# SparkFun_MOSFET_PetalV0_1.net
KiCad netlist of a schematic drawn in EAGLE
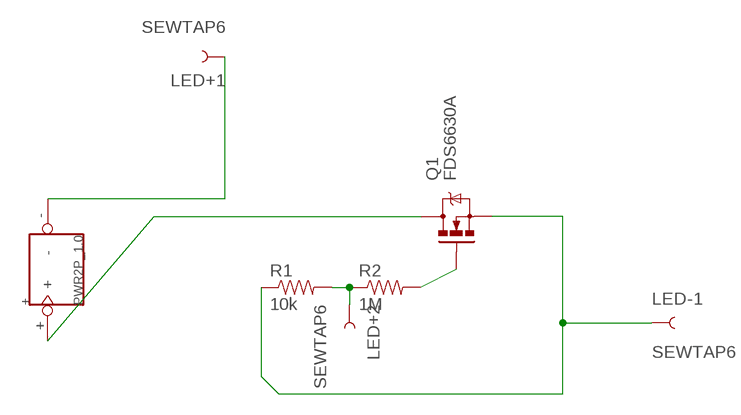
[diagram p0: schematic, sheet 1]

(export (version "E")
  (design (tool "Eeschema 10.0.6"))
  (components
    (comp (ref "+")
      (value "PWR2P_1.0")
      (footprint "eagle-import:PWR2P_1.0")
      (libsource (lib "eagle-import") (part "PWR2P_1.0"))
    )
    (comp (ref "LED+1")
      (value "SEWTAP6")
      (footprint "eagle-import:PETAL-SMALL-2SIDE")
      (libsource (lib "eagle-import") (part "SEWTAP6"))
    )
    (comp (ref "LED+2")
      (value "SEWTAP6")
      (footprint "eagle-import:PETAL-SMALL-2SIDE")
      (libsource (lib "eagle-import") (part "SEWTAP6"))
    )
    (comp (ref "LED-1")
      (value "SEWTAP6")
      (footprint "eagle-import:PETAL-SMALL-2SIDE")
      (libsource (lib "eagle-import") (part "SEWTAP6"))
    )
    (comp (ref "Q1")
      (value "FDS6630A")
      (footprint "eagle-import:SO08")
      (libsource (lib "eagle-import") (part "MOSFET-NCHANNELFDS6630A"))
    )
    (comp (ref "R1")
      (value "10k")
      (footprint "eagle-import:0402-RES")
      (libsource (lib "eagle-import") (part "RESISTOR0402-RES"))
    )
    (comp (ref "R2")
      (value "1M")
      (footprint "eagle-import:0402-RES")
      (libsource (lib "eagle-import") (part "1M-1%"))
    )
  )
  (nets
    (net (code "1") (name "Net-(+-Pad+)") (class "Default")
      (node (ref "+") (pin "+") (pinfunction "+_+") (pintype "bidirectional"))
      (node (ref "Q1") (pin "5") (pinfunction "D_5") (pintype "passive"))
      (node (ref "Q1") (pin "6") (pinfunction "D_6") (pintype "passive"))
      (node (ref "Q1") (pin "7") (pinfunction "D_7") (pintype "passive"))
      (node (ref "Q1") (pin "8") (pinfunction "D_8") (pintype "passive"))
    )
    (net (code "2") (name "Net-(+-Pad-)") (class "Default")
      (node (ref "+") (pin "-") (pinfunction "-_-") (pintype "bidirectional"))
      (node (ref "LED+1") (pin "1") (pinfunction "1_1") (pintype "bidirectional"))
    )
    (net (code "3") (name "Net-(LED+2-Pad1)") (class "Default")
      (node (ref "LED+2") (pin "1") (pinfunction "1_1") (pintype "bidirectional"))
      (node (ref "R1") (pin "2") (pinfunction "2_2") (pintype "passive"))
      (node (ref "R2") (pin "1") (pinfunction "1_1") (pintype "passive"))
    )
    (net (code "4") (name "Net-(LED-1-Pad1)") (class "Default")
      (node (ref "LED-1") (pin "1") (pinfunction "1_1") (pintype "bidirectional"))
      (node (ref "Q1") (pin "1") (pinfunction "S_1") (pintype "passive"))
      (node (ref "Q1") (pin "2") (pinfunction "S_2") (pintype "passive"))
      (node (ref "Q1") (pin "3") (pinfunction "S_3") (pintype "passive"))
      (node (ref "R1") (pin "1") (pinfunction "1_1") (pintype "passive"))
    )
    (net (code "5") (name "Net-(Q1-G)") (class "Default")
      (node (ref "Q1") (pin "4") (pinfunction "G_4") (pintype "passive"))
      (node (ref "R2") (pin "2") (pinfunction "2_2") (pintype "passive"))
    )
  )
)
